# MCU.net
KiCad netlist of a schematic drawn in Altium Designer
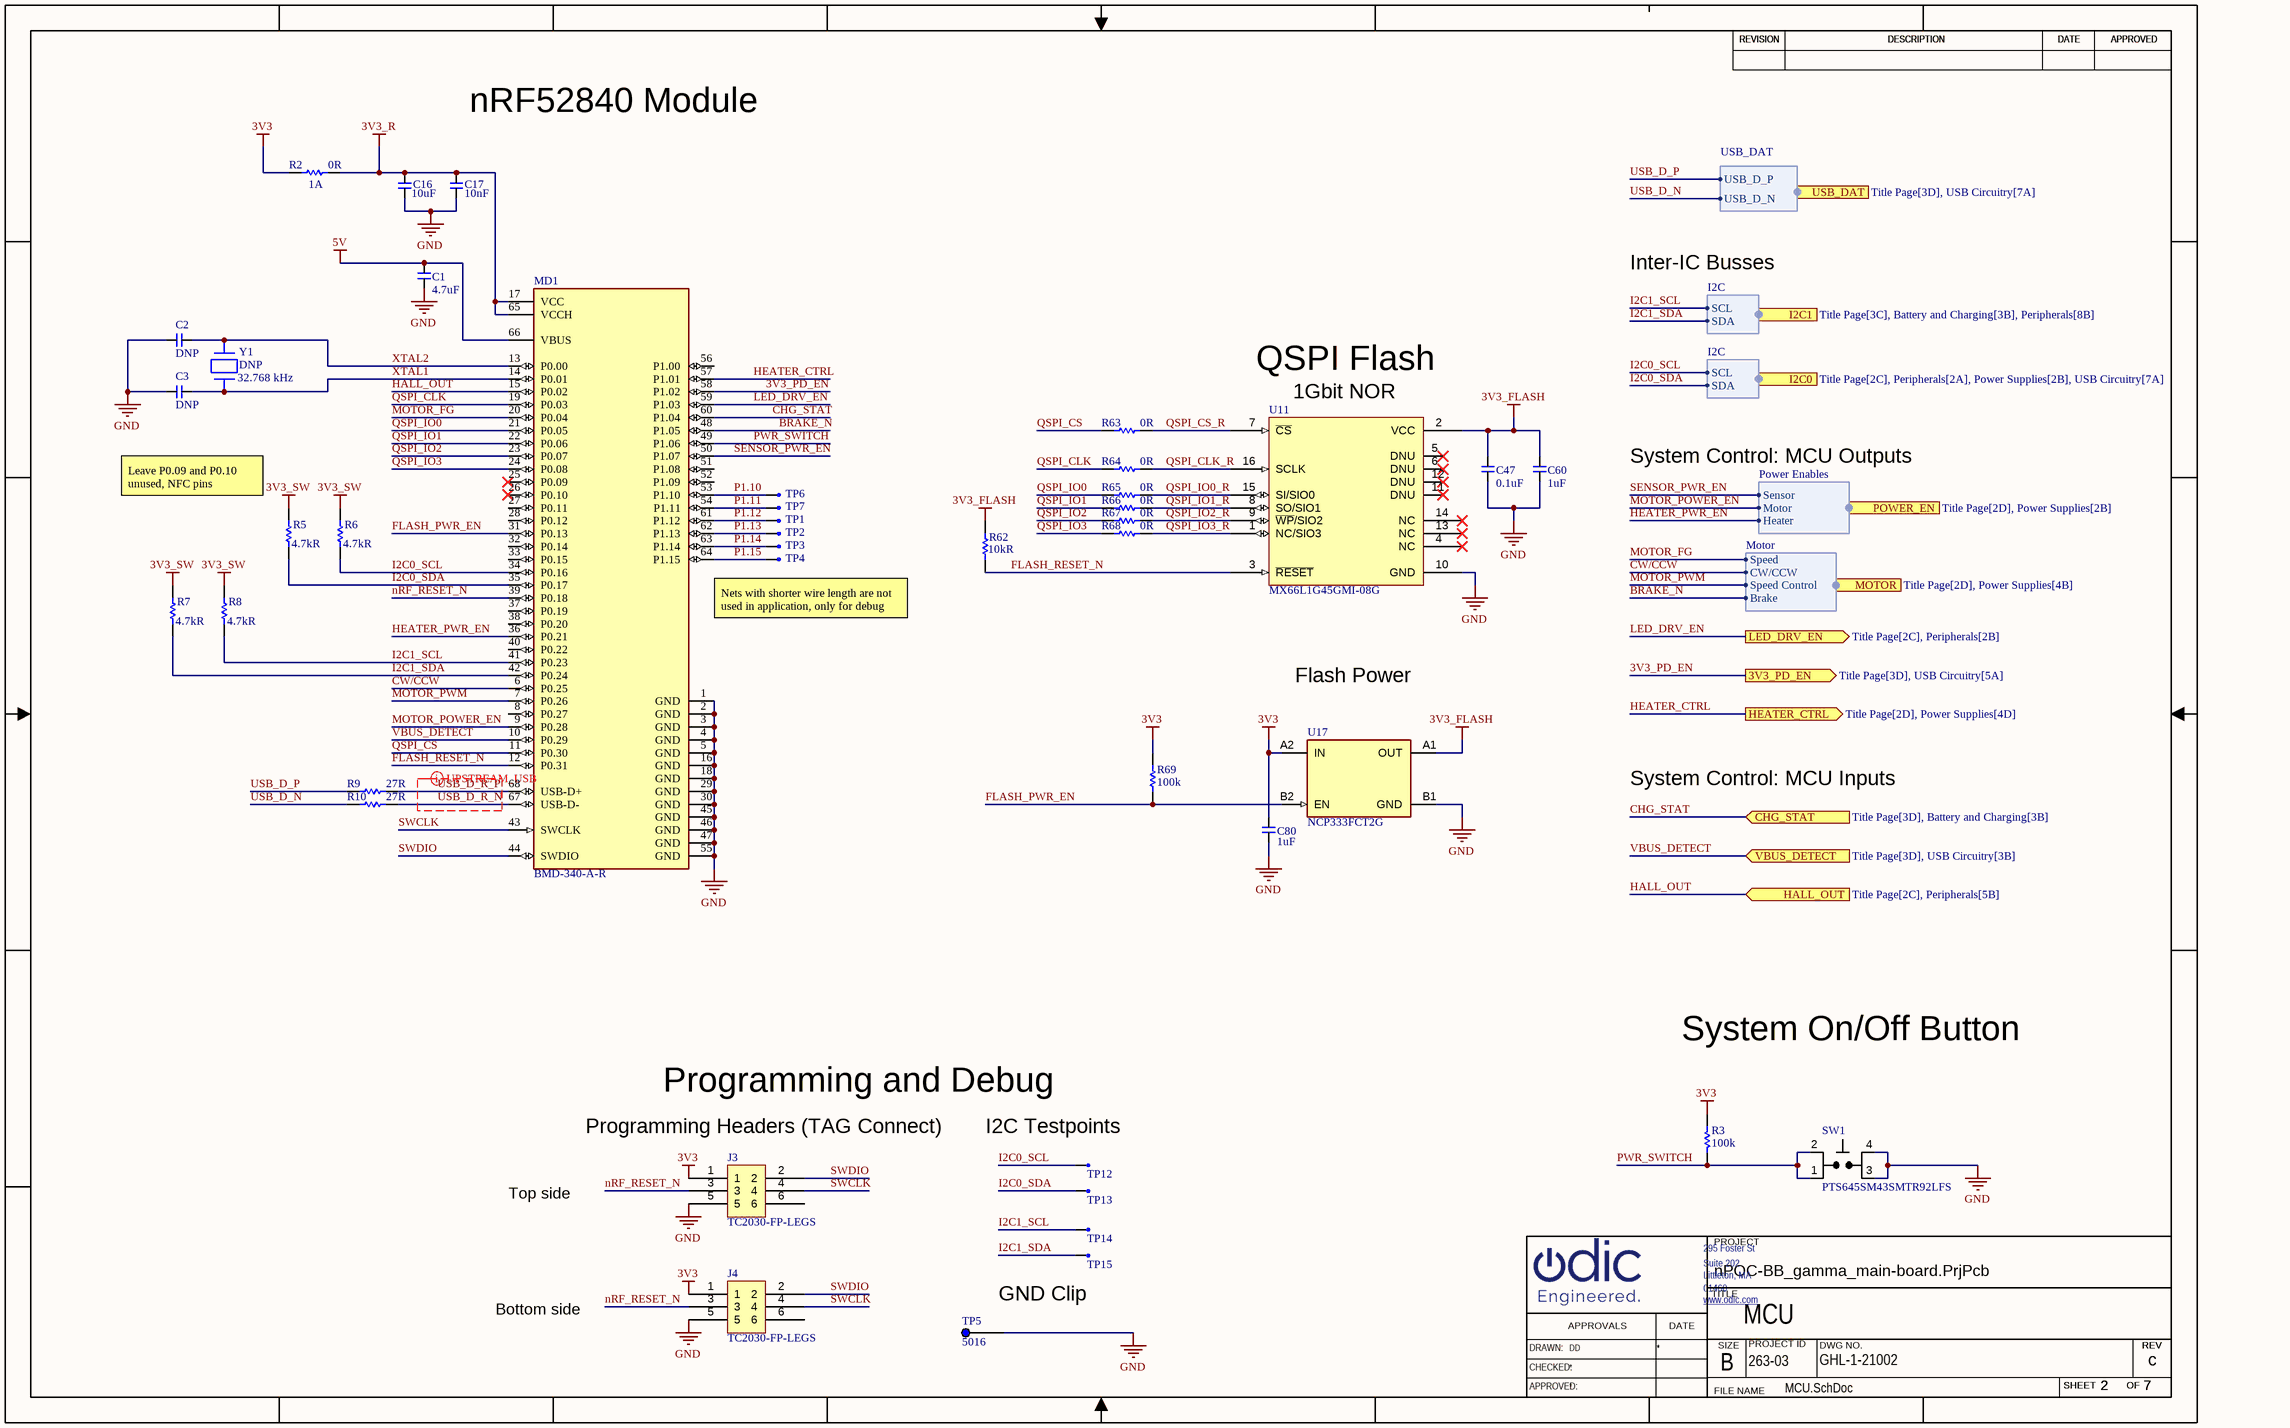
[diagram p0: MCU.SchDoc]

(export (version "E")
  (design (tool "Eeschema 10.0.6"))
  (components
    (comp (ref "C1")
      (value "4.7uF")
      (footprint "C0603")
      (description "CAP CER 4.7UF 25V X5R 0603")
      (fields (field (name "TOLERANCE") "20%"))
      (libsource (lib "Odic Inc") (part "cAP"))
    )
    (comp (ref "C2")
      (value "DNP")
      (footprint "C0402")
      (description "Blank pads for future cap placements")
      (libsource (lib "Odic Inc") (part "cAP"))
    )
    (comp (ref "C3")
      (value "DNP")
      (footprint "C0402")
      (description "Blank pads for future cap placements")
      (libsource (lib "Odic Inc") (part "cAP"))
    )
    (comp (ref "C16")
      (value "C0402_10u_6V3_20pct")
      (footprint "C0402")
      (description "Cap Ceramic 10uF 6.3V X5R 20% SMD 0402 85°C Paper T/R")
      (fields (field (name "CAPACITANCE") "10uF") (field (name "TOLERANCE") "20%"))
      (libsource (lib "Odic Inc") (part "cAP"))
    )
    (comp (ref "C17")
      (value "C0402_10n_6V3_10pct")
      (footprint "C0402")
      (description "CAP CER 10000PF 25V 10% X7R 0402")
      (fields
        (field (name "TOLERANCE") "10%")
        (field (name "CAPACITANCE") "10nF")
        (field (name "VOLTAGE") "25V")
      )
      (libsource (lib "Odic Inc") (part "cAP"))
    )
    (comp (ref "C47")
      (value "0.1uF")
      (footprint "C0402")
      (description "Cap Ceramic 0.1uF 25V X5R 10% Pad SMD 0402 Multi Layer Ceramic Capacitor (MLCC)")
      (fields (field (name "VOLTAGE") "25V") (field (name "TOLERANCE") "10%"))
      (libsource (lib "Odic Inc") (part "cAP"))
    )
    (comp (ref "C60")
      (value "1uF")
      (footprint "C0402")
      (description "CAP CER 1UF 16V X5R 0402")
      (fields (field (name "VOLTAGE") "16V") (field (name "TOLERANCE") "10%"))
      (libsource (lib "Odic Inc") (part "cAP"))
    )
    (comp (ref "C80")
      (value "C0402_1u_6V3_10pct")
      (footprint "C0402")
      (description "Cap Ceramic 1uF 6.3V X5R 10% SMD 0402 85C Paper T/R")
      (fields (field (name "CAPACITANCE") "1uF") (field (name "TOLERANCE") "10%"))
      (libsource (lib "Odic Inc") (part "cAP"))
    )
    (comp (ref "J3")
      (value "TC2030-FP-LEGS")
      (footprint "tc2030-ctx")
      (description "6 Pin Tag-Connect Header Footprint WITH HOLES FOR LEGS. Pads.")
      (libsource (lib "Odic Inc") (part "TC2030-FP-Symbol-1"))
    )
    (comp (ref "J4")
      (value "TC2030-FP-LEGS")
      (footprint "tc2030-ctx")
      (description "6 Pin Tag-Connect Header Footprint WITH HOLES FOR LEGS. Pads.")
      (libsource (lib "Odic Inc") (part "TC2030-FP-Symbol-1"))
    )
    (comp (ref "MD1")
      (value "BMD-340-A-R")
      (footprint "BMD-340-A-R")
      (description "BMD-340 Series 3.6 V 2.5 GHz -96 dBm Stand-Alone Bluetooth 5 Low Energy Module")
      (fields (field (name "MP") "BMD-330-A-R"))
      (libsource (lib "Odic Inc") (part "91e469dc995d0ea2fa1e7beafcd1398"))
    )
    (comp (ref "R2")
      (value "R0603_0R")
      (footprint "R0603")
      (description "Res Thkflm 0603 0 Ohm Jumper 1/10W 100Ppm/ C Smd Rohs Compliant: Yes")
      (fields (field (name "RESISTANCE") "0R") (field (name "CURRENT RATING") "1A"))
      (libsource (lib "Odic Inc") (part "RES"))
    )
    (comp (ref "R3")
      (value "100k")
      (footprint "R0402")
      (description "Res General Purpose Thick Film 0402 100K Ohm 1% 1/16W ±100ppm/°C Molded SMD Paper T/R")
      (fields (field (name "TOLERANCE") "1%"))
      (libsource (lib "Odic Inc") (part "RES"))
    )
    (comp (ref "R5")
      (value "R0402_4k7_1pct")
      (footprint "R0402")
      (description "RES 4.7K OHM 1% 1/16W 0402")
      (fields (field (name "TOLERANCE") "1%") (field (name "RESISTANCE") "4.7kR"))
      (libsource (lib "Odic Inc") (part "RES"))
    )
    (comp (ref "R6")
      (value "R0402_4k7_1pct")
      (footprint "R0402")
      (description "RES 4.7K OHM 1% 1/16W 0402")
      (fields (field (name "TOLERANCE") "1%") (field (name "RESISTANCE") "4.7kR"))
      (libsource (lib "Odic Inc") (part "RES"))
    )
    (comp (ref "R7")
      (value "R0402_4k7_1pct")
      (footprint "R0402")
      (description "RES 4.7K OHM 1% 1/16W 0402")
      (fields (field (name "TOLERANCE") "1%") (field (name "RESISTANCE") "4.7kR"))
      (libsource (lib "Odic Inc") (part "RES"))
    )
    (comp (ref "R8")
      (value "R0402_4k7_1pct")
      (footprint "R0402")
      (description "RES 4.7K OHM 1% 1/16W 0402")
      (fields (field (name "TOLERANCE") "1%") (field (name "RESISTANCE") "4.7kR"))
      (libsource (lib "Odic Inc") (part "RES"))
    )
    (comp (ref "R9")
      (value "27R")
      (footprint "R0402")
      (description "SMD Chip Resistor, 27 Ohm, ± 1%, 100 mW, 0402 [1005 Metric], Thick Film, Precision")
      (fields (field (name "TOLERANCE") "1%"))
      (libsource (lib "Odic Inc") (part "RES"))
    )
    (comp (ref "R10")
      (value "27R")
      (footprint "R0402")
      (description "SMD Chip Resistor, 27 Ohm, ± 1%, 100 mW, 0402 [1005 Metric], Thick Film, Precision")
      (fields (field (name "TOLERANCE") "1%"))
      (libsource (lib "Odic Inc") (part "RES"))
    )
    (comp (ref "R62")
      (value "R0402_10k_1pct")
      (footprint "R0402")
      (description "Res Thick Film 0402 10K Ohm 1% 1/16W ±100ppm/°C Molded SMD SMD T/R")
      (fields (field (name "RESISTANCE") "10kR") (field (name "TOLERANCE") "1%"))
      (libsource (lib "Odic Inc") (part "RES"))
    )
    (comp (ref "R63")
      (value "0R")
      (footprint "R0402")
      (description "RES 0 OHM JUMPER 1/16W 0402")
      (libsource (lib "Odic Inc") (part "RES"))
    )
    (comp (ref "R64")
      (value "0R")
      (footprint "R0402")
      (description "RES 0 OHM JUMPER 1/16W 0402")
      (libsource (lib "Odic Inc") (part "RES"))
    )
    (comp (ref "R65")
      (value "0R")
      (footprint "R0402")
      (description "RES 0 OHM JUMPER 1/16W 0402")
      (libsource (lib "Odic Inc") (part "RES"))
    )
    (comp (ref "R66")
      (value "0R")
      (footprint "R0402")
      (description "RES 0 OHM JUMPER 1/16W 0402")
      (libsource (lib "Odic Inc") (part "RES"))
    )
    (comp (ref "R67")
      (value "0R")
      (footprint "R0402")
      (description "RES 0 OHM JUMPER 1/16W 0402")
      (libsource (lib "Odic Inc") (part "RES"))
    )
    (comp (ref "R68")
      (value "0R")
      (footprint "R0402")
      (description "RES 0 OHM JUMPER 1/16W 0402")
      (libsource (lib "Odic Inc") (part "RES"))
    )
    (comp (ref "R69")
      (value "100k")
      (footprint "R0402")
      (description "Res General Purpose Thick Film 0402 100K Ohm 1% 1/16W ±100ppm/°C Molded SMD Paper T/R")
      (fields (field (name "TOLERANCE") "1%"))
      (libsource (lib "Odic Inc") (part "RES"))
    )
    (comp (ref "SW1")
      (value "PTS645SM43SMTR92LFS")
      (footprint "swt_pb_pts645s")
      (description "Switch Tactile N.O. SPST Round Button Gull Wing 0.05A 12VDC 100000Cycles 1.57N SMD T/R")
      (libsource (lib "Odic Inc") (part "TL3315NF160Q-Symbol-1"))
    )
    (comp (ref "TP1")
      (value "TPC30")
      (footprint "tpc30")
      (description "Test Point Circle 30")
      (libsource (lib "Odic Inc") (part "TPC"))
    )
    (comp (ref "TP2")
      (value "TPC30")
      (footprint "tpc30")
      (description "Test Point Circle 30")
      (libsource (lib "Odic Inc") (part "TPC"))
    )
    (comp (ref "TP3")
      (value "TPC30")
      (footprint "tpc30")
      (description "Test Point Circle 30")
      (libsource (lib "Odic Inc") (part "TPC"))
    )
    (comp (ref "TP4")
      (value "TPC30")
      (footprint "tpc30")
      (description "Test Point Circle 30")
      (libsource (lib "Odic Inc") (part "TPC"))
    )
    (comp (ref "TP5")
      (value "5016")
      (footprint "KEYSTONE_5016")
      (description "Test point clip, SMT Phos Bronze/Silver 1000pc Tape & Reel")
      (libsource (lib "Odic Inc") (part "5016-Symbol-1"))
    )
    (comp (ref "TP6")
      (value "TPC30")
      (footprint "tpc30")
      (description "Test Point Circle 30")
      (libsource (lib "Odic Inc") (part "TPC"))
    )
    (comp (ref "TP7")
      (value "TPC30")
      (footprint "tpc30")
      (description "Test Point Circle 30")
      (libsource (lib "Odic Inc") (part "TPC"))
    )
    (comp (ref "TP12")
      (value "TPC30")
      (footprint "tpc30")
      (description "Test Point Circle 30")
      (libsource (lib "Odic Inc") (part "TPC"))
    )
    (comp (ref "TP13")
      (value "TPC30")
      (footprint "tpc30")
      (description "Test Point Circle 30")
      (libsource (lib "Odic Inc") (part "TPC"))
    )
    (comp (ref "TP14")
      (value "TPC30")
      (footprint "tpc30")
      (description "Test Point Circle 30")
      (libsource (lib "Odic Inc") (part "TPC"))
    )
    (comp (ref "TP15")
      (value "TPC30")
      (footprint "tpc30")
      (description "Test Point Circle 30")
      (libsource (lib "Odic Inc") (part "TPC"))
    )
    (comp (ref "U11")
      (value "MX66L1G45GMI-08G")
      (footprint "sol16")
      (description "MX66L1G45G Series 1 Gb (1 G x 1) 2.7 - 3.6 V SMT Serial Flash Memory - SOP-16")
      (libsource (lib "Odic Inc") (part "MX66L1G45GMI-08G-Symbol-1"))
    )
    (comp (ref "U17")
      (value "NCP333FCT2G")
      (footprint "bga4_p743xp743_p4mm")
      (description "IC LOAD SWITCH W/DIS 1.5A 4WLCSP")
      (libsource (lib "Odic Inc") (part "97019fd276bc7644be76e1f711e9589"))
    )
    (comp (ref "Y1")
      (value "DNP")
      (footprint "xtal2_3p2x1p5")
      (description "RT3215 Series 0.032768 ±20 ppm 9pF -40°C TO +85°C SMT Tuning Fork Crystal")
      (fields (field (name "OPERATING FREQUENCY") "32.768 kHz"))
      (libsource (lib "Odic Inc") (part "Y*"))
    )
  )
  (nets
    (net (code "6") (name "/3V3_PD_EN") (class "Default")
      (node (ref "MD1") (pin "58") (pinfunction "P1.02_58") (pintype "bidirectional"))
    )
    (net (code "7") (name "/BRAKE_N") (class "Default")
      (node (ref "MD1") (pin "48") (pinfunction "P1.05_48") (pintype "bidirectional"))
    )
    (net (code "8") (name "/CHG_STAT") (class "Default")
      (node (ref "MD1") (pin "60") (pinfunction "P1.04_60") (pintype "bidirectional"))
    )
    (net (code "9") (name "/CW{slash}CCW") (class "Default")
      (node (ref "MD1") (pin "6") (pinfunction "P0.25_6") (pintype "bidirectional"))
    )
    (net (code "10") (name "/FLASH_PWR_EN") (class "Default")
      (node (ref "MD1") (pin "31") (pinfunction "P0.13_31") (pintype "bidirectional"))
      (node (ref "R69") (pin "2") (pinfunction "2_2") (pintype "passive"))
      (node (ref "U17") (pin "B2") (pinfunction "EN_B2") (pintype "input"))
    )
    (net (code "11") (name "/FLASH_RESET_N") (class "Default")
      (node (ref "MD1") (pin "12") (pinfunction "P0.31_12") (pintype "bidirectional"))
      (node (ref "R62") (pin "2") (pinfunction "2_2") (pintype "passive"))
      (node (ref "U11") (pin "3") (pinfunction "~{RESET}_3") (pintype "input"))
    )
    (net (code "12") (name "/HALL_OUT") (class "Default")
      (node (ref "MD1") (pin "15") (pinfunction "P0.02_15") (pintype "bidirectional"))
    )
    (net (code "13") (name "/HEATER_CTRL") (class "Default")
      (node (ref "MD1") (pin "57") (pinfunction "P1.01_57") (pintype "bidirectional"))
    )
    (net (code "14") (name "/HEATER_PWR_EN") (class "Default")
      (node (ref "MD1") (pin "36") (pinfunction "P0.21_36") (pintype "bidirectional"))
    )
    (net (code "15") (name "/I2C0_SCL") (class "Default")
      (node (ref "MD1") (pin "34") (pinfunction "P0.16_34") (pintype "bidirectional"))
      (node (ref "R6") (pin "1") (pinfunction "1_1") (pintype "passive"))
      (node (ref "TP12") (pin "1") (pinfunction "1_1") (pintype "passive"))
    )
    (net (code "16") (name "/I2C0_SDA") (class "Default")
      (node (ref "MD1") (pin "35") (pinfunction "P0.17_35") (pintype "bidirectional"))
      (node (ref "R5") (pin "1") (pinfunction "1_1") (pintype "passive"))
      (node (ref "TP13") (pin "1") (pinfunction "1_1") (pintype "passive"))
    )
    (net (code "17") (name "/I2C1_SCL") (class "Default")
      (node (ref "MD1") (pin "41") (pinfunction "P0.23_41") (pintype "bidirectional"))
      (node (ref "R8") (pin "1") (pinfunction "1_1") (pintype "passive"))
      (node (ref "TP14") (pin "1") (pinfunction "1_1") (pintype "passive"))
    )
    (net (code "18") (name "/I2C1_SDA") (class "Default")
      (node (ref "MD1") (pin "42") (pinfunction "P0.24_42") (pintype "bidirectional"))
      (node (ref "R7") (pin "1") (pinfunction "1_1") (pintype "passive"))
      (node (ref "TP15") (pin "1") (pinfunction "1_1") (pintype "passive"))
    )
    (net (code "19") (name "/LED_DRV_EN") (class "Default")
      (node (ref "MD1") (pin "59") (pinfunction "P1.03_59") (pintype "bidirectional"))
    )
    (net (code "20") (name "/MOTOR_FG") (class "Default")
      (node (ref "MD1") (pin "20") (pinfunction "P0.04_20") (pintype "bidirectional"))
    )
    (net (code "21") (name "/MOTOR_POWER_EN") (class "Default")
      (node (ref "MD1") (pin "9") (pinfunction "P0.28_9") (pintype "bidirectional"))
    )
    (net (code "22") (name "/MOTOR_PWM") (class "Default")
      (node (ref "MD1") (pin "7") (pinfunction "P0.26_7") (pintype "bidirectional"))
    )
    (net (code "23") (name "/P1.10") (class "Default")
      (node (ref "MD1") (pin "53") (pinfunction "P1.10_53") (pintype "bidirectional"))
      (node (ref "TP6") (pin "1") (pinfunction "1_1") (pintype "passive"))
    )
    (net (code "24") (name "/P1.11") (class "Default")
      (node (ref "MD1") (pin "54") (pinfunction "P1.11_54") (pintype "bidirectional"))
      (node (ref "TP7") (pin "1") (pinfunction "1_1") (pintype "passive"))
    )
    (net (code "25") (name "/P1.12") (class "Default")
      (node (ref "MD1") (pin "61") (pinfunction "P1.12_61") (pintype "bidirectional"))
      (node (ref "TP1") (pin "1") (pinfunction "1_1") (pintype "passive"))
    )
    (net (code "26") (name "/P1.13") (class "Default")
      (node (ref "MD1") (pin "62") (pinfunction "P1.13_62") (pintype "bidirectional"))
      (node (ref "TP2") (pin "1") (pinfunction "1_1") (pintype "passive"))
    )
    (net (code "27") (name "/P1.14") (class "Default")
      (node (ref "MD1") (pin "63") (pinfunction "P1.14_63") (pintype "bidirectional"))
      (node (ref "TP3") (pin "1") (pinfunction "1_1") (pintype "passive"))
    )
    (net (code "28") (name "/P1.15") (class "Default")
      (node (ref "MD1") (pin "64") (pinfunction "P1.15_64") (pintype "bidirectional"))
      (node (ref "TP4") (pin "1") (pinfunction "1_1") (pintype "passive"))
    )
    (net (code "29") (name "/PWR_SWITCH") (class "Default")
      (node (ref "MD1") (pin "49") (pinfunction "P1.06_49") (pintype "bidirectional"))
      (node (ref "R3") (pin "1") (pinfunction "1_1") (pintype "passive"))
      (node (ref "SW1") (pin "1") (pinfunction "1_1") (pintype "passive"))
      (node (ref "SW1") (pin "2") (pinfunction "2_2") (pintype "passive"))
    )
    (net (code "30") (name "/QSPI_CLK") (class "Default")
      (node (ref "MD1") (pin "19") (pinfunction "P0.03_19") (pintype "bidirectional"))
      (node (ref "R64") (pin "1") (pinfunction "1_1") (pintype "passive"))
    )
    (net (code "31") (name "/QSPI_CLK_R") (class "Default")
      (node (ref "R64") (pin "2") (pinfunction "2_2") (pintype "passive"))
      (node (ref "U11") (pin "16") (pinfunction "SCLK_16") (pintype "input"))
    )
    (net (code "32") (name "/QSPI_CS") (class "Default")
      (node (ref "MD1") (pin "11") (pinfunction "P0.30_11") (pintype "bidirectional"))
      (node (ref "R63") (pin "1") (pinfunction "1_1") (pintype "passive"))
    )
    (net (code "33") (name "/QSPI_CS_R") (class "Default")
      (node (ref "R63") (pin "2") (pinfunction "2_2") (pintype "passive"))
      (node (ref "U11") (pin "7") (pinfunction "~{CS}_7") (pintype "input"))
    )
    (net (code "34") (name "/QSPI_IO0") (class "Default")
      (node (ref "MD1") (pin "21") (pinfunction "P0.05_21") (pintype "bidirectional"))
      (node (ref "R65") (pin "1") (pinfunction "1_1") (pintype "passive"))
    )
    (net (code "35") (name "/QSPI_IO0_R") (class "Default")
      (node (ref "R65") (pin "2") (pinfunction "2_2") (pintype "passive"))
      (node (ref "U11") (pin "15") (pinfunction "SI/SIO0_15") (pintype "bidirectional"))
    )
    (net (code "36") (name "/QSPI_IO1") (class "Default")
      (node (ref "MD1") (pin "22") (pinfunction "P0.06_22") (pintype "bidirectional"))
      (node (ref "R66") (pin "1") (pinfunction "1_1") (pintype "passive"))
    )
    (net (code "37") (name "/QSPI_IO1_R") (class "Default")
      (node (ref "R66") (pin "2") (pinfunction "2_2") (pintype "passive"))
      (node (ref "U11") (pin "8") (pinfunction "SO/SIO1_8") (pintype "bidirectional"))
    )
    (net (code "38") (name "/QSPI_IO2") (class "Default")
      (node (ref "MD1") (pin "23") (pinfunction "P0.07_23") (pintype "bidirectional"))
      (node (ref "R67") (pin "1") (pinfunction "1_1") (pintype "passive"))
    )
    (net (code "39") (name "/QSPI_IO2_R") (class "Default")
      (node (ref "R67") (pin "2") (pinfunction "2_2") (pintype "passive"))
      (node (ref "U11") (pin "9") (pinfunction "~{WP}/SIO2_9") (pintype "bidirectional"))
    )
    (net (code "40") (name "/QSPI_IO3") (class "Default")
      (node (ref "MD1") (pin "24") (pinfunction "P0.08_24") (pintype "bidirectional"))
      (node (ref "R68") (pin "1") (pinfunction "1_1") (pintype "passive"))
    )
    (net (code "41") (name "/QSPI_IO3_R") (class "Default")
      (node (ref "R68") (pin "2") (pinfunction "2_2") (pintype "passive"))
      (node (ref "U11") (pin "1") (pinfunction "NC/SIO3_1") (pintype "bidirectional"))
    )
    (net (code "42") (name "/SENSOR_PWR_EN") (class "Default")
      (node (ref "MD1") (pin "50") (pinfunction "P1.07_50") (pintype "bidirectional"))
    )
    (net (code "43") (name "/SWCLK") (class "Default")
      (node (ref "J3") (pin "4") (pinfunction "4_4") (pintype "passive"))
      (node (ref "J4") (pin "4") (pinfunction "4_4") (pintype "passive"))
      (node (ref "MD1") (pin "43") (pinfunction "SWCLK_43") (pintype "input"))
    )
    (net (code "44") (name "/SWDIO") (class "Default")
      (node (ref "J3") (pin "2") (pinfunction "2_2") (pintype "passive"))
      (node (ref "J4") (pin "2") (pinfunction "2_2") (pintype "passive"))
      (node (ref "MD1") (pin "44") (pinfunction "SWDIO_44") (pintype "bidirectional"))
    )
    (net (code "45") (name "/USB_D_N") (class "Default")
      (node (ref "R10") (pin "1") (pinfunction "1_1") (pintype "passive"))
    )
    (net (code "46") (name "/USB_D_P") (class "Default")
      (node (ref "R9") (pin "1") (pinfunction "1_1") (pintype "passive"))
    )
    (net (code "47") (name "/USB_D_R_N") (class "Default")
      (node (ref "MD1") (pin "67") (pinfunction "USB-D-_67") (pintype "bidirectional"))
      (node (ref "R10") (pin "2") (pinfunction "2_2") (pintype "passive"))
    )
    (net (code "48") (name "/USB_D_R_P") (class "Default")
      (node (ref "MD1") (pin "68") (pinfunction "USB-D+_68") (pintype "bidirectional"))
      (node (ref "R9") (pin "2") (pinfunction "2_2") (pintype "passive"))
    )
    (net (code "49") (name "/VBUS_DETECT") (class "Default")
      (node (ref "MD1") (pin "10") (pinfunction "P0.29_10") (pintype "bidirectional"))
    )
    (net (code "50") (name "/XTAL1") (class "Default")
      (node (ref "C3") (pin "2") (pinfunction "2_2") (pintype "passive"))
      (node (ref "MD1") (pin "14") (pinfunction "P0.01_14") (pintype "bidirectional"))
      (node (ref "Y1") (pin "2") (pinfunction "2_2") (pintype "passive"))
    )
    (net (code "51") (name "/XTAL2") (class "Default")
      (node (ref "C2") (pin "2") (pinfunction "2_2") (pintype "passive"))
      (node (ref "MD1") (pin "13") (pinfunction "P0.00_13") (pintype "bidirectional"))
      (node (ref "Y1") (pin "1") (pinfunction "1_1") (pintype "passive"))
    )
    (net (code "52") (name "/nRF_RESET_N") (class "Default")
      (node (ref "J3") (pin "3") (pinfunction "3_3") (pintype "passive"))
      (node (ref "J4") (pin "3") (pinfunction "3_3") (pintype "passive"))
      (node (ref "MD1") (pin "39") (pinfunction "P0.18_39") (pintype "bidirectional"))
    )
    (net (code "57") (name "3V3") (class "Default")
      (node (ref "C80") (pin "2") (pinfunction "2_2") (pintype "passive"))
      (node (ref "J3") (pin "1") (pinfunction "1_1") (pintype "passive"))
      (node (ref "J4") (pin "1") (pinfunction "1_1") (pintype "passive"))
      (node (ref "R2") (pin "1") (pinfunction "1_1") (pintype "passive"))
      (node (ref "R3") (pin "2") (pinfunction "2_2") (pintype "passive"))
      (node (ref "R69") (pin "1") (pinfunction "1_1") (pintype "passive"))
      (node (ref "U17") (pin "A2") (pinfunction "IN_A2") (pintype "power_in"))
    )
    (net (code "58") (name "3V3_FLASH") (class "Default")
      (node (ref "C47") (pin "2") (pinfunction "2_2") (pintype "passive"))
      (node (ref "C60") (pin "2") (pinfunction "2_2") (pintype "passive"))
      (node (ref "R62") (pin "1") (pinfunction "1_1") (pintype "passive"))
      (node (ref "U11") (pin "2") (pinfunction "VCC_2") (pintype "power_in"))
      (node (ref "U17") (pin "A1") (pinfunction "OUT_A1") (pintype "power_in"))
    )
    (net (code "59") (name "3V3_R") (class "Default")
      (node (ref "C16") (pin "2") (pinfunction "2_2") (pintype "passive"))
      (node (ref "C17") (pin "2") (pinfunction "2_2") (pintype "passive"))
      (node (ref "MD1") (pin "17") (pinfunction "VCC_17") (pintype "power_in"))
      (node (ref "MD1") (pin "65") (pinfunction "VCCH_65") (pintype "power_in"))
      (node (ref "R2") (pin "2") (pinfunction "2_2") (pintype "passive"))
    )
    (net (code "60") (name "3V3_SW") (class "Default")
      (node (ref "R5") (pin "2") (pinfunction "2_2") (pintype "passive"))
      (node (ref "R6") (pin "2") (pinfunction "2_2") (pintype "passive"))
      (node (ref "R7") (pin "2") (pinfunction "2_2") (pintype "passive"))
      (node (ref "R8") (pin "2") (pinfunction "2_2") (pintype "passive"))
    )
    (net (code "61") (name "5V") (class "Default")
      (node (ref "C1") (pin "2") (pinfunction "2_2") (pintype "passive"))
      (node (ref "MD1") (pin "66") (pinfunction "VBUS_66") (pintype "power_in"))
    )
    (net (code "62") (name "GND") (class "Default")
      (node (ref "C1") (pin "1") (pinfunction "1_1") (pintype "passive"))
      (node (ref "C16") (pin "1") (pinfunction "1_1") (pintype "passive"))
      (node (ref "C17") (pin "1") (pinfunction "1_1") (pintype "passive"))
      (node (ref "C2") (pin "1") (pinfunction "1_1") (pintype "passive"))
      (node (ref "C3") (pin "1") (pinfunction "1_1") (pintype "passive"))
      (node (ref "C47") (pin "1") (pinfunction "1_1") (pintype "passive"))
      (node (ref "C60") (pin "1") (pinfunction "1_1") (pintype "passive"))
      (node (ref "C80") (pin "1") (pinfunction "1_1") (pintype "passive"))
      (node (ref "J3") (pin "5") (pinfunction "5_5") (pintype "passive"))
      (node (ref "J4") (pin "5") (pinfunction "5_5") (pintype "passive"))
      (node (ref "MD1") (pin "1") (pinfunction "GND_1") (pintype "power_in"))
      (node (ref "MD1") (pin "16") (pinfunction "GND_16") (pintype "power_in"))
      (node (ref "MD1") (pin "18") (pinfunction "GND_18") (pintype "power_in"))
      (node (ref "MD1") (pin "2") (pinfunction "GND_2") (pintype "power_in"))
      (node (ref "MD1") (pin "29") (pinfunction "GND_29") (pintype "power_in"))
      (node (ref "MD1") (pin "3") (pinfunction "GND_3") (pintype "power_in"))
      (node (ref "MD1") (pin "30") (pinfunction "GND_30") (pintype "power_in"))
      (node (ref "MD1") (pin "4") (pinfunction "GND_4") (pintype "power_in"))
      (node (ref "MD1") (pin "45") (pinfunction "GND_45") (pintype "power_in"))
      (node (ref "MD1") (pin "46") (pinfunction "GND_46") (pintype "power_in"))
      (node (ref "MD1") (pin "47") (pinfunction "GND_47") (pintype "power_in"))
      (node (ref "MD1") (pin "5") (pinfunction "GND_5") (pintype "power_in"))
      (node (ref "MD1") (pin "55") (pinfunction "GND_55") (pintype "power_in"))
      (node (ref "SW1") (pin "3") (pinfunction "3_3") (pintype "passive"))
      (node (ref "SW1") (pin "4") (pinfunction "4_4") (pintype "passive"))
      (node (ref "TP5") (pin "1") (pinfunction "1_1") (pintype "passive"))
      (node (ref "U11") (pin "10") (pinfunction "GND_10") (pintype "passive"))
      (node (ref "U17") (pin "B1") (pinfunction "GND_B1") (pintype "power_in"))
    )
    (net (code "63") (name "unconnected-(J3-Pad6)") (class "Default")
      (node (ref "J3") (pin "6") (pinfunction "6_6") (pintype "passive"))
    )
    (net (code "64") (name "unconnected-(J4-Pad6)") (class "Default")
      (node (ref "J4") (pin "6") (pinfunction "6_6") (pintype "passive"))
    )
    (net (code "65") (name "unconnected-(MD1-P0.09-Pad25)") (class "Default")
      (node (ref "MD1") (pin "25") (pinfunction "P0.09_25") (pintype "bidirectional+no_connect"))
    )
    (net (code "66") (name "unconnected-(MD1-P0.10-Pad26)") (class "Default")
      (node (ref "MD1") (pin "26") (pinfunction "P0.10_26") (pintype "bidirectional+no_connect"))
    )
    (net (code "67") (name "unconnected-(MD1-P0.11-Pad27)") (class "Default")
      (node (ref "MD1") (pin "27") (pinfunction "P0.11_27") (pintype "bidirectional"))
    )
    (net (code "68") (name "unconnected-(MD1-P0.12-Pad28)") (class "Default")
      (node (ref "MD1") (pin "28") (pinfunction "P0.12_28") (pintype "bidirectional"))
    )
    (net (code "69") (name "unconnected-(MD1-P0.14-Pad32)") (class "Default")
      (node (ref "MD1") (pin "32") (pinfunction "P0.14_32") (pintype "bidirectional"))
    )
    (net (code "70") (name "unconnected-(MD1-P0.15-Pad33)") (class "Default")
      (node (ref "MD1") (pin "33") (pinfunction "P0.15_33") (pintype "bidirectional"))
    )
    (net (code "71") (name "unconnected-(MD1-P0.19-Pad37)") (class "Default")
      (node (ref "MD1") (pin "37") (pinfunction "P0.19_37") (pintype "bidirectional"))
    )
    (net (code "72") (name "unconnected-(MD1-P0.20-Pad38)") (class "Default")
      (node (ref "MD1") (pin "38") (pinfunction "P0.20_38") (pintype "bidirectional"))
    )
    (net (code "73") (name "unconnected-(MD1-P0.22-Pad40)") (class "Default")
      (node (ref "MD1") (pin "40") (pinfunction "P0.22_40") (pintype "bidirectional"))
    )
    (net (code "74") (name "unconnected-(MD1-P0.27-Pad8)") (class "Default")
      (node (ref "MD1") (pin "8") (pinfunction "P0.27_8") (pintype "bidirectional"))
    )
    (net (code "75") (name "unconnected-(MD1-P1.00-Pad56)") (class "Default")
      (node (ref "MD1") (pin "56") (pinfunction "P1.00_56") (pintype "bidirectional"))
    )
    (net (code "76") (name "unconnected-(MD1-P1.08-Pad51)") (class "Default")
      (node (ref "MD1") (pin "51") (pinfunction "P1.08_51") (pintype "bidirectional"))
    )
    (net (code "77") (name "unconnected-(MD1-P1.09-Pad52)") (class "Default")
      (node (ref "MD1") (pin "52") (pinfunction "P1.09_52") (pintype "bidirectional"))
    )
    (net (code "78") (name "unconnected-(U11-DNU-Pad5)") (class "Default")
      (node (ref "U11") (pin "5") (pinfunction "DNU_5") (pintype "passive+no_connect"))
    )
    (net (code "79") (name "unconnected-(U11-DNU-Pad6)") (class "Default")
      (node (ref "U11") (pin "6") (pinfunction "DNU_6") (pintype "passive+no_connect"))
    )
    (net (code "80") (name "unconnected-(U11-DNU-Pad11)") (class "Default")
      (node (ref "U11") (pin "11") (pinfunction "DNU_11") (pintype "passive+no_connect"))
    )
    (net (code "81") (name "unconnected-(U11-DNU-Pad12)") (class "Default")
      (node (ref "U11") (pin "12") (pinfunction "DNU_12") (pintype "passive+no_connect"))
    )
    (net (code "82") (name "unconnected-(U11-NC-Pad4)") (class "Default")
      (node (ref "U11") (pin "4") (pinfunction "NC_4") (pintype "passive+no_connect"))
    )
    (net (code "83") (name "unconnected-(U11-NC-Pad13)") (class "Default")
      (node (ref "U11") (pin "13") (pinfunction "NC_13") (pintype "passive+no_connect"))
    )
    (net (code "84") (name "unconnected-(U11-NC-Pad14)") (class "Default")
      (node (ref "U11") (pin "14") (pinfunction "NC_14") (pintype "passive+no_connect"))
    )
  )
)
